# berry_3_0.net
KiCad netlist of a schematic drawn in EAGLE
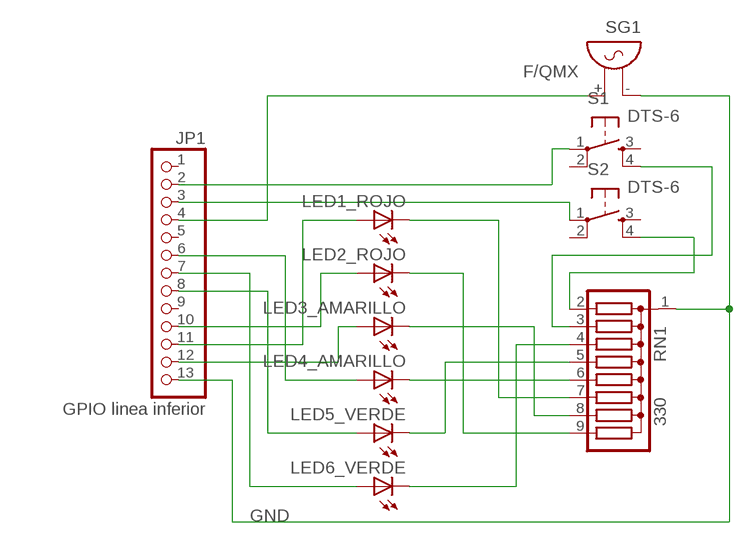
[diagram p0: schematic, sheet 1]

(export (version "E")
  (design (tool "Eeschema 10.0.6"))
  (components
    (comp (ref "JP1")
      (value "GPIO linea inferior")
      (footprint "eagle-import:1X13")
      (libsource (lib "eagle-import") (part "PINHD-1X13"))
    )
    (comp (ref "LED1_ROJO")
      (value "LED5MM")
      (footprint "eagle-import:LED5MM")
      (libsource (lib "eagle-import") (part "LED5MM"))
    )
    (comp (ref "LED2_ROJO")
      (value "LED5MM")
      (footprint "eagle-import:LED5MM")
      (libsource (lib "eagle-import") (part "LED5MM"))
    )
    (comp (ref "LED3_AMARILLO")
      (value "LED5MM")
      (footprint "eagle-import:LED5MM")
      (libsource (lib "eagle-import") (part "LED5MM"))
    )
    (comp (ref "LED4_AMARILLO")
      (value "LED5MM")
      (footprint "eagle-import:LED5MM")
      (libsource (lib "eagle-import") (part "LED5MM"))
    )
    (comp (ref "LED5_VERDE")
      (value "LED5MM")
      (footprint "eagle-import:LED5MM")
      (libsource (lib "eagle-import") (part "LED5MM"))
    )
    (comp (ref "LED6_VERDE")
      (value "LED5MM")
      (footprint "eagle-import:LED5MM")
      (libsource (lib "eagle-import") (part "LED5MM"))
    )
    (comp (ref "RN1")
      (value "330")
      (footprint "eagle-import:SIL9")
      (libsource (lib "eagle-import") (part "G08R"))
    )
    (comp (ref "S1")
      (value "DTS-6")
      (footprint "eagle-import:DTS-6")
      (libsource (lib "eagle-import") (part "DTS-6"))
    )
    (comp (ref "S2")
      (value "DTS-6")
      (footprint "eagle-import:DTS-6")
      (libsource (lib "eagle-import") (part "DTS-6"))
    )
    (comp (ref "SG1")
      (value "F/QMX")
      (footprint "eagle-import:F_QMX")
      (libsource (lib "eagle-import") (part "F/QMX"))
    )
  )
  (nets
    (net (code "1") (name "/GND") (class "Default")
      (node (ref "JP1") (pin "13") (pinfunction "13_13") (pintype "passive"))
      (node (ref "RN1") (pin "1") (pinfunction "1_1") (pintype "passive"))
      (node (ref "SG1") (pin "-") (pinfunction "1_-") (pintype "passive"))
    )
    (net (code "2") (name "Net-(JP1-Pad2)") (class "Default")
      (node (ref "JP1") (pin "2") (pinfunction "2_2") (pintype "passive"))
      (node (ref "S1") (pin "1") (pinfunction "1_1") (pintype "passive"))
    )
    (net (code "3") (name "Net-(JP1-Pad3)") (class "Default")
      (node (ref "JP1") (pin "3") (pinfunction "3_3") (pintype "passive"))
      (node (ref "S2") (pin "1") (pinfunction "1_1") (pintype "passive"))
    )
    (net (code "4") (name "Net-(JP1-Pad6)") (class "Default")
      (node (ref "JP1") (pin "6") (pinfunction "6_6") (pintype "passive"))
      (node (ref "LED4_AMARILLO") (pin "A") (pinfunction "A_A") (pintype "passive"))
    )
    (net (code "5") (name "Net-(JP1-Pad7)") (class "Default")
      (node (ref "JP1") (pin "7") (pinfunction "7_7") (pintype "passive"))
      (node (ref "LED6_VERDE") (pin "A") (pinfunction "A_A") (pintype "passive"))
    )
    (net (code "6") (name "Net-(JP1-Pad8)") (class "Default")
      (node (ref "JP1") (pin "8") (pinfunction "8_8") (pintype "passive"))
      (node (ref "LED5_VERDE") (pin "A") (pinfunction "A_A") (pintype "passive"))
    )
    (net (code "7") (name "Net-(JP1-Pad10)") (class "Default")
      (node (ref "JP1") (pin "10") (pinfunction "10_10") (pintype "passive"))
      (node (ref "LED2_ROJO") (pin "A") (pinfunction "A_A") (pintype "passive"))
    )
    (net (code "8") (name "Net-(JP1-Pad11)") (class "Default")
      (node (ref "JP1") (pin "11") (pinfunction "11_11") (pintype "passive"))
      (node (ref "LED1_ROJO") (pin "A") (pinfunction "A_A") (pintype "passive"))
    )
    (net (code "9") (name "Net-(JP1-Pad12)") (class "Default")
      (node (ref "JP1") (pin "12") (pinfunction "12_12") (pintype "passive"))
      (node (ref "LED3_AMARILLO") (pin "A") (pinfunction "A_A") (pintype "passive"))
    )
    (net (code "10") (name "Net-(LED1_ROJO-C)") (class "Default")
      (node (ref "LED1_ROJO") (pin "K") (pinfunction "C_K") (pintype "passive"))
      (node (ref "RN1") (pin "7") (pinfunction "7_7") (pintype "passive"))
    )
    (net (code "11") (name "Net-(LED2_ROJO-C)") (class "Default")
      (node (ref "LED2_ROJO") (pin "K") (pinfunction "C_K") (pintype "passive"))
      (node (ref "RN1") (pin "9") (pinfunction "9_9") (pintype "passive"))
    )
    (net (code "12") (name "Net-(LED3_AMARILLO-C)") (class "Default")
      (node (ref "LED3_AMARILLO") (pin "K") (pinfunction "C_K") (pintype "passive"))
      (node (ref "RN1") (pin "8") (pinfunction "8_8") (pintype "passive"))
    )
    (net (code "13") (name "Net-(LED4_AMARILLO-C)") (class "Default")
      (node (ref "LED4_AMARILLO") (pin "K") (pinfunction "C_K") (pintype "passive"))
      (node (ref "RN1") (pin "6") (pinfunction "6_6") (pintype "passive"))
    )
    (net (code "14") (name "Net-(LED5_VERDE-C)") (class "Default")
      (node (ref "LED5_VERDE") (pin "K") (pinfunction "C_K") (pintype "passive"))
      (node (ref "RN1") (pin "5") (pinfunction "5_5") (pintype "passive"))
    )
    (net (code "15") (name "Net-(LED6_VERDE-C)") (class "Default")
      (node (ref "LED6_VERDE") (pin "K") (pinfunction "C_K") (pintype "passive"))
      (node (ref "RN1") (pin "4") (pinfunction "4_4") (pintype "passive"))
    )
    (net (code "16") (name "Net-(RN1-Pad2)") (class "Default")
      (node (ref "RN1") (pin "2") (pinfunction "2_2") (pintype "passive"))
      (node (ref "S2") (pin "4") (pinfunction "4_4") (pintype "passive"))
    )
    (net (code "17") (name "Net-(RN1-Pad3)") (class "Default")
      (node (ref "RN1") (pin "3") (pinfunction "3_3") (pintype "passive"))
      (node (ref "S1") (pin "4") (pinfunction "4_4") (pintype "passive"))
    )
    (net (code "18") (name "Net-(SG1-2)") (class "Default")
      (node (ref "JP1") (pin "4") (pinfunction "4_4") (pintype "passive"))
      (node (ref "SG1") (pin "+") (pinfunction "2_+") (pintype "passive"))
    )
    (net (code "19") (name "unconnected-(JP1-Pad1)") (class "Default")
      (node (ref "JP1") (pin "1") (pinfunction "1_1") (pintype "passive"))
    )
    (net (code "20") (name "unconnected-(JP1-Pad5)") (class "Default")
      (node (ref "JP1") (pin "5") (pinfunction "5_5") (pintype "passive"))
    )
    (net (code "21") (name "unconnected-(JP1-Pad9)") (class "Default")
      (node (ref "JP1") (pin "9") (pinfunction "9_9") (pintype "passive"))
    )
    (net (code "22") (name "unconnected-(S1-Pad2)") (class "Default")
      (node (ref "S1") (pin "2") (pinfunction "2_2") (pintype "passive"))
    )
    (net (code "23") (name "unconnected-(S1-Pad3)") (class "Default")
      (node (ref "S1") (pin "3") (pinfunction "3_3") (pintype "passive"))
    )
    (net (code "24") (name "unconnected-(S2-Pad2)") (class "Default")
      (node (ref "S2") (pin "2") (pinfunction "2_2") (pintype "passive"))
    )
    (net (code "25") (name "unconnected-(S2-Pad3)") (class "Default")
      (node (ref "S2") (pin "3") (pinfunction "3_3") (pintype "passive"))
    )
  )
)
